# ADTPCB.net
KiCad netlist of a schematic drawn in Altium Designer
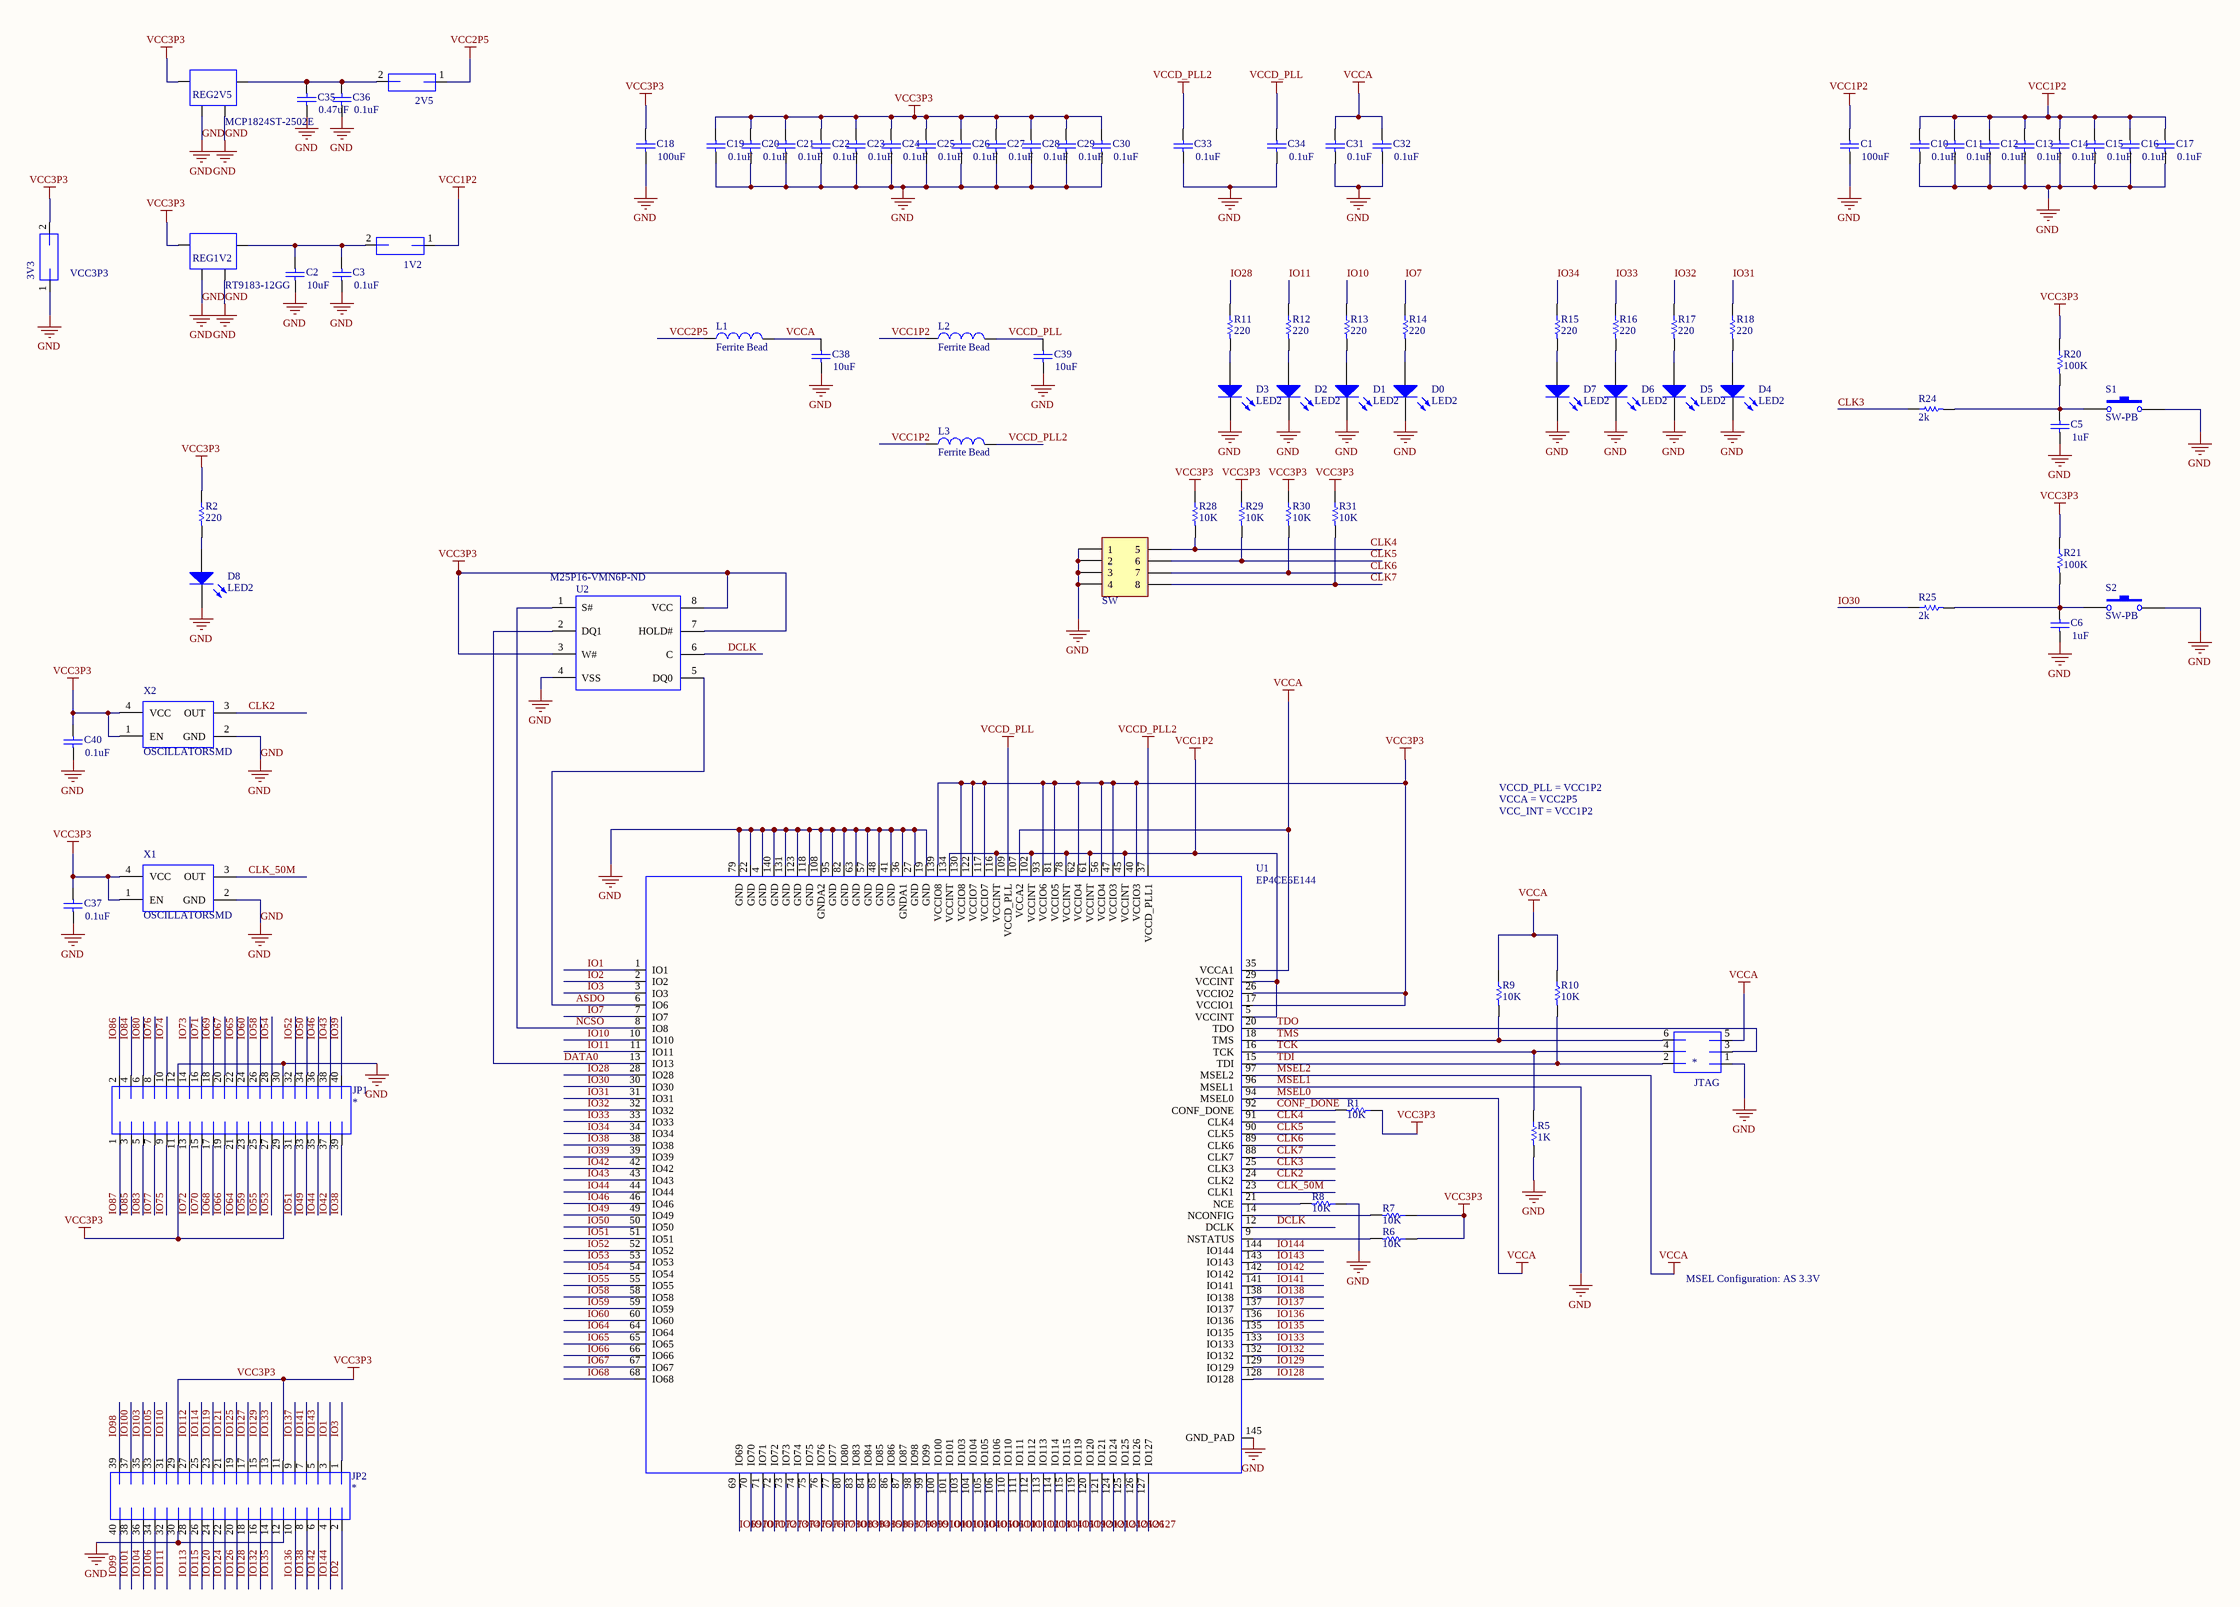
[diagram p0: ADTPCB.SchDoc]

(export (version "E")
  (design (tool "Eeschema 10.0.6"))
  (components
    (comp (ref "1V2")
      (value "1V2")
      (footprint "HDR1X2")
      (description "CONN HEADER 36POS .100 VERT TIN")
      (libsource (lib "jumper") (part "JP1Q"))
    )
    (comp (ref "2V5")
      (value "2V5")
      (footprint "HDR1X2")
      (description "CONN HEADER 36POS .100 VERT TIN")
      (libsource (lib "jumper") (part "JP1Q"))
    )
    (comp (ref "3V3")
      (value "VCC3P3")
      (footprint "HDR1X2")
      (description "CONN HEADER 36POS .100 VERT TIN")
      (libsource (lib "jumper") (part "JP1Q"))
    )
    (comp (ref "C1")
      (value "100uF")
      (footprint "C1206")
      (description "CAP CER 100UF 6.3V Y5V 1206")
      (fields (field (name "Comment") "Cap"))
      (libsource (lib "Miscellaneous Devices") (part "Cap"))
    )
    (comp (ref "C2")
      (value "10uF")
      (footprint "C0805")
      (description "CAP CER 10UF 10V Y5V 0805")
      (fields (field (name "Comment") "Cap"))
      (libsource (lib "Miscellaneous Devices") (part "Cap"))
    )
    (comp (ref "C3")
      (value "0.1uF")
      (footprint "C0805")
      (description "CAP CER 0.1UF 16V 10% X7R 0805")
      (fields (field (name "Comment") "Cap"))
      (libsource (lib "Miscellaneous Devices") (part "Cap"))
    )
    (comp (ref "C5")
      (value "1uF")
      (footprint "C0805")
      (description "CAP CER 1UF 16V Y5V 0805")
      (fields (field (name "Comment") "Cap"))
      (libsource (lib "Miscellaneous Devices") (part "Cap"))
    )
    (comp (ref "C6")
      (value "1uF")
      (footprint "C0805")
      (description "CAP CER 1UF 16V Y5V 0805")
      (fields (field (name "Comment") "Cap"))
      (libsource (lib "Miscellaneous Devices") (part "Cap"))
    )
    (comp (ref "C10")
      (value "0.1uF")
      (footprint "C0805")
      (description "CAP CER 0.1UF 16V 10% X7R 0805")
      (fields (field (name "Comment") "Cap"))
      (libsource (lib "Miscellaneous Devices") (part "Cap"))
    )
    (comp (ref "C11")
      (value "0.1uF")
      (footprint "C0805")
      (description "CAP CER 0.1UF 16V 10% X7R 0805")
      (fields (field (name "Comment") "Cap"))
      (libsource (lib "Miscellaneous Devices") (part "Cap"))
    )
    (comp (ref "C12")
      (value "0.1uF")
      (footprint "C0805")
      (description "CAP CER 0.1UF 16V 10% X7R 0805")
      (fields (field (name "Comment") "Cap"))
      (libsource (lib "Miscellaneous Devices") (part "Cap"))
    )
    (comp (ref "C13")
      (value "0.1uF")
      (footprint "C0805")
      (description "CAP CER 0.1UF 16V 10% X7R 0805")
      (fields (field (name "Comment") "Cap"))
      (libsource (lib "Miscellaneous Devices") (part "Cap"))
    )
    (comp (ref "C14")
      (value "0.1uF")
      (footprint "C0805")
      (description "CAP CER 0.1UF 16V 10% X7R 0805")
      (fields (field (name "Comment") "Cap"))
      (libsource (lib "Miscellaneous Devices") (part "Cap"))
    )
    (comp (ref "C15")
      (value "0.1uF")
      (footprint "C0805")
      (description "CAP CER 0.1UF 16V 10% X7R 0805")
      (fields (field (name "Comment") "Cap"))
      (libsource (lib "Miscellaneous Devices") (part "Cap"))
    )
    (comp (ref "C16")
      (value "0.1uF")
      (footprint "C0805")
      (description "CAP CER 0.1UF 16V 10% X7R 0805")
      (fields (field (name "Comment") "Cap"))
      (libsource (lib "Miscellaneous Devices") (part "Cap"))
    )
    (comp (ref "C17")
      (value "0.1uF")
      (footprint "C0805")
      (description "CAP CER 0.1UF 16V 10% X7R 0805")
      (fields (field (name "Comment") "Cap"))
      (libsource (lib "Miscellaneous Devices") (part "Cap"))
    )
    (comp (ref "C18")
      (value "100uF")
      (footprint "C1206")
      (description "CAP CER 100UF 6.3V Y5V 1206")
      (fields (field (name "Comment") "Cap"))
      (libsource (lib "Miscellaneous Devices") (part "Cap"))
    )
    (comp (ref "C19")
      (value "0.1uF")
      (footprint "C0805")
      (description "CAP CER 0.1UF 16V 10% X7R 0805")
      (fields (field (name "Comment") "Cap"))
      (libsource (lib "Miscellaneous Devices") (part "Cap"))
    )
    (comp (ref "C20")
      (value "0.1uF")
      (footprint "C0805")
      (description "CAP CER 0.1UF 16V 10% X7R 0805")
      (fields (field (name "Comment") "Cap"))
      (libsource (lib "Miscellaneous Devices") (part "Cap"))
    )
    (comp (ref "C21")
      (value "0.1uF")
      (footprint "C0805")
      (description "CAP CER 0.1UF 16V 10% X7R 0805")
      (fields (field (name "Comment") "Cap"))
      (libsource (lib "Miscellaneous Devices") (part "Cap"))
    )
    (comp (ref "C22")
      (value "0.1uF")
      (footprint "C0805")
      (description "CAP CER 0.1UF 16V 10% X7R 0805")
      (fields (field (name "Comment") "Cap"))
      (libsource (lib "Miscellaneous Devices") (part "Cap"))
    )
    (comp (ref "C23")
      (value "0.1uF")
      (footprint "C0805")
      (description "CAP CER 0.1UF 16V 10% X7R 0805")
      (fields (field (name "Comment") "Cap"))
      (libsource (lib "Miscellaneous Devices") (part "Cap"))
    )
    (comp (ref "C24")
      (value "0.1uF")
      (footprint "C0805")
      (description "CAP CER 0.1UF 16V 10% X7R 0805")
      (fields (field (name "Comment") "Cap"))
      (libsource (lib "Miscellaneous Devices") (part "Cap"))
    )
    (comp (ref "C25")
      (value "0.1uF")
      (footprint "C0805")
      (description "CAP CER 0.1UF 16V 10% X7R 0805")
      (fields (field (name "Comment") "Cap"))
      (libsource (lib "Miscellaneous Devices") (part "Cap"))
    )
    (comp (ref "C26")
      (value "0.1uF")
      (footprint "C0805")
      (description "CAP CER 0.1UF 16V 10% X7R 0805")
      (fields (field (name "Comment") "Cap"))
      (libsource (lib "Miscellaneous Devices") (part "Cap"))
    )
    (comp (ref "C27")
      (value "0.1uF")
      (footprint "C0805")
      (description "CAP CER 0.1UF 16V 10% X7R 0805")
      (fields (field (name "Comment") "Cap"))
      (libsource (lib "Miscellaneous Devices") (part "Cap"))
    )
    (comp (ref "C28")
      (value "0.1uF")
      (footprint "C0805")
      (description "CAP CER 0.1UF 16V 10% X7R 0805")
      (fields (field (name "Comment") "Cap"))
      (libsource (lib "Miscellaneous Devices") (part "Cap"))
    )
    (comp (ref "C29")
      (value "0.1uF")
      (footprint "C0805")
      (description "CAP CER 0.1UF 16V 10% X7R 0805")
      (fields (field (name "Comment") "Cap"))
      (libsource (lib "Miscellaneous Devices") (part "Cap"))
    )
    (comp (ref "C30")
      (value "0.1uF")
      (footprint "C0805")
      (description "CAP CER 0.1UF 16V 10% X7R 0805")
      (fields (field (name "Comment") "Cap"))
      (libsource (lib "Miscellaneous Devices") (part "Cap"))
    )
    (comp (ref "C31")
      (value "0.1uF")
      (footprint "C0805")
      (description "CAP CER 0.1UF 16V 10% X7R 0805")
      (fields (field (name "Comment") "Cap"))
      (libsource (lib "Miscellaneous Devices") (part "Cap"))
    )
    (comp (ref "C32")
      (value "0.1uF")
      (footprint "C0805")
      (description "CAP CER 0.1UF 16V 10% X7R 0805")
      (fields (field (name "Comment") "Cap"))
      (libsource (lib "Miscellaneous Devices") (part "Cap"))
    )
    (comp (ref "C33")
      (value "0.1uF")
      (footprint "C0805")
      (description "CAP CER 0.1UF 16V 10% X7R 0805")
      (fields (field (name "Comment") "Cap"))
      (libsource (lib "Miscellaneous Devices") (part "Cap"))
    )
    (comp (ref "C34")
      (value "0.1uF")
      (footprint "C0805")
      (description "CAP CER 0.1UF 16V 10% X7R 0805")
      (fields (field (name "Comment") "Cap"))
      (libsource (lib "Miscellaneous Devices") (part "Cap"))
    )
    (comp (ref "C35")
      (value "0.47uF")
      (footprint "C0805")
      (description "CAP CER 0.47UF 16V 10% X7R 0805")
      (fields (field (name "Comment") "Cap"))
      (libsource (lib "Miscellaneous Devices") (part "Cap"))
    )
    (comp (ref "C36")
      (value "0.1uF")
      (footprint "C0805")
      (description "CAP CER 0.1UF 16V 10% X7R 0805")
      (fields (field (name "Comment") "Cap"))
      (libsource (lib "Miscellaneous Devices") (part "Cap"))
    )
    (comp (ref "C37")
      (value "0.1uF")
      (footprint "C0805")
      (description "CAP CER 0.1UF 16V 10% X7R 0805")
      (fields (field (name "Comment") "Cap"))
      (libsource (lib "Miscellaneous Devices") (part "Cap"))
    )
    (comp (ref "C38")
      (value "10uF")
      (footprint "C0805")
      (description "CAP CER 10UF 10V Y5V 0805")
      (fields (field (name "Comment") "Cap"))
      (libsource (lib "Miscellaneous Devices") (part "Cap"))
    )
    (comp (ref "C39")
      (value "10uF")
      (footprint "C0805")
      (description "CAP CER 10UF 10V Y5V 0805")
      (fields (field (name "Comment") "Cap"))
      (libsource (lib "Miscellaneous Devices") (part "Cap"))
    )
    (comp (ref "C40")
      (value "0.1uF")
      (footprint "C0805")
      (description "CAP CER 0.1UF 16V 10% X7R 0805")
      (fields (field (name "Comment") "Cap"))
      (libsource (lib "Miscellaneous Devices") (part "Cap"))
    )
    (comp (ref "D0")
      (value "LED2")
      (footprint "CD2012-0805")
      (description "LED GREEN CLEAR THIN 0805 SMD")
      (libsource (lib "Miscellaneous Devices") (part "LED2"))
    )
    (comp (ref "D1")
      (value "LED2")
      (footprint "CD2012-0805")
      (description "LED GREEN CLEAR THIN 0805 SMD")
      (libsource (lib "Miscellaneous Devices") (part "LED2"))
    )
    (comp (ref "D2")
      (value "LED2")
      (footprint "CD2012-0805")
      (description "LED GREEN CLEAR THIN 0805 SMD")
      (libsource (lib "Miscellaneous Devices") (part "LED2"))
    )
    (comp (ref "D3")
      (value "LED2")
      (footprint "CD2012-0805")
      (description "LED GREEN CLEAR THIN 0805 SMD")
      (libsource (lib "Miscellaneous Devices") (part "LED2"))
    )
    (comp (ref "D4")
      (value "LED2")
      (footprint "CD2012-0805")
      (description "LED GREEN CLEAR THIN 0805 SMD")
      (libsource (lib "Miscellaneous Devices") (part "LED2"))
    )
    (comp (ref "D5")
      (value "LED2")
      (footprint "CD2012-0805")
      (description "LED GREEN CLEAR THIN 0805 SMD")
      (libsource (lib "Miscellaneous Devices") (part "LED2"))
    )
    (comp (ref "D6")
      (value "LED2")
      (footprint "CD2012-0805")
      (description "LED GREEN CLEAR THIN 0805 SMD")
      (libsource (lib "Miscellaneous Devices") (part "LED2"))
    )
    (comp (ref "D7")
      (value "LED2")
      (footprint "CD2012-0805")
      (description "LED GREEN CLEAR THIN 0805 SMD")
      (libsource (lib "Miscellaneous Devices") (part "LED2"))
    )
    (comp (ref "D8")
      (value "LED2")
      (footprint "CD2012-0805")
      (description "LED GREEN CLEAR THIN 0805 SMD")
      (libsource (lib "Miscellaneous Devices") (part "LED2"))
    )
    (comp (ref "JP1")
      (value "*")
      (footprint "HDR2X20")
      (description "CONN HEADER 36POS .100 VERT TIN")
      (libsource (lib "ADTBoard") (part "JP20Q"))
    )
    (comp (ref "JP2")
      (value "*")
      (footprint "HDR2X20")
      (description "CONN HEADER 36POS .100 VERT TIN")
      (libsource (lib "ADTBoard") (part "JP20Q"))
    )
    (comp (ref "JTAG")
      (value "*")
      (footprint "HDR1X6")
      (description "CONN HEADER 36POS .100 VERT TIN")
      (libsource (lib "jumper") (part "JP3Q"))
    )
    (comp (ref "L1")
      (value "Ferrite Bead")
      (footprint "2029")
      (description "FERRITE CHIP BEAD 600 OHM SMD")
      (libsource (lib "Miscellaneous Devices") (part "Inductor"))
    )
    (comp (ref "L2")
      (value "Ferrite Bead")
      (footprint "2029")
      (description "FERRITE CHIP BEAD 600 OHM SMD")
      (libsource (lib "Miscellaneous Devices") (part "Inductor"))
    )
    (comp (ref "L3")
      (value "Ferrite Bead")
      (footprint "2029")
      (description "FERRITE CHIP BEAD 600 OHM SMD")
      (libsource (lib "Miscellaneous Devices") (part "Inductor"))
    )
    (comp (ref "R1")
      (value "10K")
      (footprint "6-0805_L")
      (description "RES 10K OHM 1/8W 5% 0805 SMD")
      (fields (field (name "Comment") "Res Semi"))
      (libsource (lib "Miscellaneous Devices") (part "Res Semi"))
    )
    (comp (ref "R2")
      (value "220")
      (footprint "6-0805_L")
      (description "RES 220 OHM 1/8W 5% 0805 SMD")
      (fields (field (name "Comment") "Res Semi"))
      (libsource (lib "Miscellaneous Devices") (part "Res Semi"))
    )
    (comp (ref "R5")
      (value "1K")
      (footprint "6-0805_L")
      (description "RES 1.0K OHM 1/8W 5% 0805 SMD")
      (fields (field (name "Comment") "Res Semi"))
      (libsource (lib "Miscellaneous Devices") (part "Res Semi"))
    )
    (comp (ref "R6")
      (value "10K")
      (footprint "6-0805_L")
      (description "RES 10K OHM 1/8W 5% 0805 SMD")
      (fields (field (name "Comment") "Res Semi"))
      (libsource (lib "Miscellaneous Devices") (part "Res Semi"))
    )
    (comp (ref "R7")
      (value "10K")
      (footprint "6-0805_L")
      (description "RES 10K OHM 1/8W 5% 0805 SMD")
      (fields (field (name "Comment") "Res Semi"))
      (libsource (lib "Miscellaneous Devices") (part "Res Semi"))
    )
    (comp (ref "R8")
      (value "10K")
      (footprint "6-0805_L")
      (description "RES 10K OHM 1/8W 5% 0805 SMD")
      (fields (field (name "Comment") "Res Semi"))
      (libsource (lib "Miscellaneous Devices") (part "Res Semi"))
    )
    (comp (ref "R9")
      (value "10K")
      (footprint "6-0805_L")
      (description "RES 10K OHM 1/8W 5% 0805 SMD")
      (fields (field (name "Comment") "Res Semi"))
      (libsource (lib "Miscellaneous Devices") (part "Res Semi"))
    )
    (comp (ref "R10")
      (value "10K")
      (footprint "6-0805_L")
      (description "RES 10K OHM 1/8W 5% 0805 SMD")
      (fields (field (name "Comment") "Res Semi"))
      (libsource (lib "Miscellaneous Devices") (part "Res Semi"))
    )
    (comp (ref "R11")
      (value "220")
      (footprint "6-0805_L")
      (description "RES 220 OHM 1/8W 5% 0805 SMD")
      (fields (field (name "Comment") "Res Semi"))
      (libsource (lib "Miscellaneous Devices") (part "Res Semi"))
    )
    (comp (ref "R12")
      (value "220")
      (footprint "6-0805_L")
      (description "RES 220 OHM 1/8W 5% 0805 SMD")
      (fields (field (name "Comment") "Res Semi"))
      (libsource (lib "Miscellaneous Devices") (part "Res Semi"))
    )
    (comp (ref "R13")
      (value "220")
      (footprint "6-0805_L")
      (description "RES 220 OHM 1/8W 5% 0805 SMD")
      (fields (field (name "Comment") "Res Semi"))
      (libsource (lib "Miscellaneous Devices") (part "Res Semi"))
    )
    (comp (ref "R14")
      (value "220")
      (footprint "6-0805_L")
      (description "RES 220 OHM 1/8W 5% 0805 SMD")
      (fields (field (name "Comment") "Res Semi"))
      (libsource (lib "Miscellaneous Devices") (part "Res Semi"))
    )
    (comp (ref "R15")
      (value "220")
      (footprint "6-0805_L")
      (description "RES 220 OHM 1/8W 5% 0805 SMD")
      (fields (field (name "Comment") "Res Semi"))
      (libsource (lib "Miscellaneous Devices") (part "Res Semi"))
    )
    (comp (ref "R16")
      (value "220")
      (footprint "6-0805_L")
      (description "RES 220 OHM 1/8W 5% 0805 SMD")
      (fields (field (name "Comment") "Res Semi"))
      (libsource (lib "Miscellaneous Devices") (part "Res Semi"))
    )
    (comp (ref "R17")
      (value "220")
      (footprint "6-0805_L")
      (description "RES 220 OHM 1/8W 5% 0805 SMD")
      (fields (field (name "Comment") "Res Semi"))
      (libsource (lib "Miscellaneous Devices") (part "Res Semi"))
    )
    (comp (ref "R18")
      (value "220")
      (footprint "6-0805_L")
      (description "RES 220 OHM 1/8W 5% 0805 SMD")
      (fields (field (name "Comment") "Res Semi"))
      (libsource (lib "Miscellaneous Devices") (part "Res Semi"))
    )
    (comp (ref "R20")
      (value "100K")
      (footprint "6-0805_L")
      (description "RES 100K OHM 1/8W 5% 0805 SMD")
      (fields (field (name "Comment") "Res Semi"))
      (libsource (lib "Miscellaneous Devices") (part "Res Semi"))
    )
    (comp (ref "R21")
      (value "100K")
      (footprint "6-0805_L")
      (description "RES 100K OHM 1/8W 5% 0805 SMD")
      (fields (field (name "Comment") "Res Semi"))
      (libsource (lib "Miscellaneous Devices") (part "Res Semi"))
    )
    (comp (ref "R24")
      (value "2k")
      (footprint "6-0805_L")
      (description "RES 2K OHM 1/8W 5% 0805 SMD")
      (fields (field (name "Comment") "Res Semi"))
      (libsource (lib "Miscellaneous Devices") (part "Res Semi"))
    )
    (comp (ref "R25")
      (value "2k")
      (footprint "6-0805_L")
      (description "RES 2K OHM 1/8W 5% 0805 SMD")
      (fields (field (name "Comment") "Res Semi"))
      (libsource (lib "Miscellaneous Devices") (part "Res Semi"))
    )
    (comp (ref "R28")
      (value "10K")
      (footprint "6-0805_L")
      (description "RES 10K OHM 1/8W 5% 0805 SMD")
      (fields (field (name "Comment") "Res Semi"))
      (libsource (lib "Miscellaneous Devices") (part "Res Semi"))
    )
    (comp (ref "R29")
      (value "10K")
      (footprint "6-0805_L")
      (description "RES 10K OHM 1/8W 5% 0805 SMD")
      (fields (field (name "Comment") "Res Semi"))
      (libsource (lib "Miscellaneous Devices") (part "Res Semi"))
    )
    (comp (ref "R30")
      (value "10K")
      (footprint "6-0805_L")
      (description "RES 10K OHM 1/8W 5% 0805 SMD")
      (fields (field (name "Comment") "Res Semi"))
      (libsource (lib "Miscellaneous Devices") (part "Res Semi"))
    )
    (comp (ref "R31")
      (value "10K")
      (footprint "6-0805_L")
      (description "RES 10K OHM 1/8W 5% 0805 SMD")
      (fields (field (name "Comment") "Res Semi"))
      (libsource (lib "Miscellaneous Devices") (part "Res Semi"))
    )
    (comp (ref "REG1V2")
      (value "RT9183-12GG")
      (footprint "SOT223_M")
      (description "IC REG LDO 1.2V 1.5A SOT223")
      (libsource (lib "ADTBoard") (part "RT9183-12GG"))
    )
    (comp (ref "REG2V5")
      (value "MCP1824ST-2502E")
      (footprint "SOT223_M")
      (description "IC REG LDO 2.5V .3A SOT223-3")
      (libsource (lib "ADTBoard") (part "RT9183-12GG"))
    )
    (comp (ref "S1")
      (value "SW-PB")
      (footprint "EVQ-P7C01K")
      (description "SWITCH TACTILE SPST-NO 0.05A 12V")
      (libsource (lib "Miscellaneous Devices") (part "SW-PB"))
    )
    (comp (ref "S2")
      (value "SW-PB")
      (footprint "EVQ-P7C01K")
      (description "SWITCH TACTILE SPST-NO 0.05A 12V")
      (libsource (lib "Miscellaneous Devices") (part "SW-PB"))
    )
    (comp (ref "SW")
      (value "DIP")
      (footprint "DIP")
      (description "SWITCH DIP HALF PITCH 4POS")
      (libsource (lib "ADTPCB") (part "DIP"))
    )
    (comp (ref "U1")
      (value "EP4CE6E144")
      (footprint "EQFP144_M")
      (description "IC CYCLONE IV E FPGA 144EQFP")
      (libsource (lib "ADTPCB") (part "EP4CE6E144"))
    )
    (comp (ref "U2")
      (value "*")
      (footprint "SO8_M")
      (description "IC FLASH 16MBIT 75MHZ 8SOIC")
      (fields (field (name "SUPPLIER PART NUMBER 1") "M25P16-VMN6P-ND"))
      (libsource (lib "ADTBoard") (part "M25P16"))
    )
    (comp (ref "X1")
      (value "OSCILLATORSMD")
      (footprint "Oscillator SMD")
      (description "OSCILLATOR 50.00MHZ SMD")
      (libsource (lib "ADTPCB") (part "OSCILLATORSMD"))
    )
    (comp (ref "X2")
      (value "OSCILLATORSMD")
      (footprint "Oscillator SMD")
      (description "OSCILLATOR 50.00MHZ SMD")
      (libsource (lib "ADTPCB") (part "OSCILLATORSMD"))
    )
  )
  (nets
    (net (code "1") (name "/ASDO") (class "Default")
      (node (ref "U1") (pin "6") (pinfunction "IO6_6") (pintype "passive"))
      (node (ref "U2") (pin "5") (pinfunction "DQ0_5") (pintype "passive"))
    )
    (net (code "2") (name "/CLK2") (class "Default")
      (node (ref "U1") (pin "24") (pinfunction "CLK2_24") (pintype "passive"))
      (node (ref "X2") (pin "3") (pinfunction "OUT_3") (pintype "passive"))
    )
    (net (code "3") (name "/CLK3") (class "Default")
      (node (ref "R24") (pin "1") (pinfunction "1_1") (pintype "passive"))
      (node (ref "U1") (pin "25") (pinfunction "CLK3_25") (pintype "passive"))
    )
    (net (code "4") (name "/CLK4") (class "Default")
      (node (ref "R28") (pin "2") (pinfunction "2_2") (pintype "passive"))
      (node (ref "SW") (pin "5") (pinfunction "5_5") (pintype "passive"))
      (node (ref "U1") (pin "91") (pinfunction "CLK4_91") (pintype "passive"))
    )
    (net (code "5") (name "/CLK5") (class "Default")
      (node (ref "R29") (pin "2") (pinfunction "2_2") (pintype "passive"))
      (node (ref "SW") (pin "6") (pinfunction "6_6") (pintype "passive"))
      (node (ref "U1") (pin "90") (pinfunction "CLK5_90") (pintype "passive"))
    )
    (net (code "6") (name "/CLK6") (class "Default")
      (node (ref "R30") (pin "2") (pinfunction "2_2") (pintype "passive"))
      (node (ref "SW") (pin "7") (pinfunction "7_7") (pintype "passive"))
      (node (ref "U1") (pin "89") (pinfunction "CLK6_89") (pintype "passive"))
    )
    (net (code "7") (name "/CLK7") (class "Default")
      (node (ref "R31") (pin "2") (pinfunction "2_2") (pintype "passive"))
      (node (ref "SW") (pin "8") (pinfunction "8_8") (pintype "passive"))
      (node (ref "U1") (pin "88") (pinfunction "CLK7_88") (pintype "passive"))
    )
    (net (code "8") (name "/CLK_50M") (class "Default")
      (node (ref "U1") (pin "23") (pinfunction "CLK1_23") (pintype "passive"))
      (node (ref "X1") (pin "3") (pinfunction "OUT_3") (pintype "passive"))
    )
    (net (code "9") (name "/CONF_DONE") (class "Default")
      (node (ref "R1") (pin "2") (pinfunction "2_2") (pintype "passive"))
      (node (ref "U1") (pin "92") (pinfunction "CONF_DONE_92") (pintype "passive"))
    )
    (net (code "10") (name "/DATA0") (class "Default")
      (node (ref "U1") (pin "13") (pinfunction "IO13_13") (pintype "passive"))
      (node (ref "U2") (pin "2") (pinfunction "DQ1_2") (pintype "passive"))
    )
    (net (code "11") (name "/DCLK") (class "Default")
      (node (ref "U1") (pin "12") (pinfunction "DCLK_12") (pintype "passive"))
      (node (ref "U2") (pin "6") (pinfunction "C_6") (pintype "passive"))
    )
    (net (code "12") (name "/IO1") (class "Default")
      (node (ref "JP2") (pin "3") (pinfunction "3_3") (pintype "passive"))
      (node (ref "U1") (pin "1") (pinfunction "IO1_1") (pintype "passive"))
    )
    (net (code "13") (name "/IO2") (class "Default")
      (node (ref "JP2") (pin "2") (pinfunction "2_2") (pintype "passive"))
      (node (ref "U1") (pin "2") (pinfunction "IO2_2") (pintype "passive"))
    )
    (net (code "14") (name "/IO3") (class "Default")
      (node (ref "JP2") (pin "1") (pinfunction "1_1") (pintype "passive"))
      (node (ref "U1") (pin "3") (pinfunction "IO3_3") (pintype "passive"))
    )
    (net (code "15") (name "/IO7") (class "Default")
      (node (ref "R14") (pin "1") (pinfunction "1_1") (pintype "passive"))
      (node (ref "U1") (pin "7") (pinfunction "IO7_7") (pintype "passive"))
    )
    (net (code "16") (name "/IO10") (class "Default")
      (node (ref "R13") (pin "1") (pinfunction "1_1") (pintype "passive"))
      (node (ref "U1") (pin "10") (pinfunction "IO10_10") (pintype "passive"))
    )
    (net (code "17") (name "/IO11") (class "Default")
      (node (ref "R12") (pin "1") (pinfunction "1_1") (pintype "passive"))
      (node (ref "U1") (pin "11") (pinfunction "IO11_11") (pintype "passive"))
    )
    (net (code "18") (name "/IO28") (class "Default")
      (node (ref "R11") (pin "1") (pinfunction "1_1") (pintype "passive"))
      (node (ref "U1") (pin "28") (pinfunction "IO28_28") (pintype "passive"))
    )
    (net (code "19") (name "/IO30") (class "Default")
      (node (ref "R25") (pin "1") (pinfunction "1_1") (pintype "passive"))
      (node (ref "U1") (pin "30") (pinfunction "IO30_30") (pintype "passive"))
    )
    (net (code "20") (name "/IO31") (class "Default")
      (node (ref "R18") (pin "1") (pinfunction "1_1") (pintype "passive"))
      (node (ref "U1") (pin "31") (pinfunction "IO31_31") (pintype "passive"))
    )
    (net (code "21") (name "/IO32") (class "Default")
      (node (ref "R17") (pin "1") (pinfunction "1_1") (pintype "passive"))
      (node (ref "U1") (pin "32") (pinfunction "IO32_32") (pintype "passive"))
    )
    (net (code "22") (name "/IO33") (class "Default")
      (node (ref "R16") (pin "1") (pinfunction "1_1") (pintype "passive"))
      (node (ref "U1") (pin "33") (pinfunction "IO33_33") (pintype "passive"))
    )
    (net (code "23") (name "/IO34") (class "Default")
      (node (ref "R15") (pin "1") (pinfunction "1_1") (pintype "passive"))
      (node (ref "U1") (pin "34") (pinfunction "IO34_34") (pintype "passive"))
    )
    (net (code "24") (name "/IO38") (class "Default")
      (node (ref "JP1") (pin "39") (pinfunction "39_39") (pintype "passive"))
      (node (ref "U1") (pin "38") (pinfunction "IO38_38") (pintype "passive"))
    )
    (net (code "25") (name "/IO39") (class "Default")
      (node (ref "JP1") (pin "40") (pinfunction "40_40") (pintype "passive"))
      (node (ref "U1") (pin "39") (pinfunction "IO39_39") (pintype "passive"))
    )
    (net (code "26") (name "/IO42") (class "Default")
      (node (ref "JP1") (pin "37") (pinfunction "37_37") (pintype "passive"))
      (node (ref "U1") (pin "42") (pinfunction "IO42_42") (pintype "passive"))
    )
    (net (code "27") (name "/IO43") (class "Default")
      (node (ref "JP1") (pin "38") (pinfunction "38_38") (pintype "passive"))
      (node (ref "U1") (pin "43") (pinfunction "IO43_43") (pintype "passive"))
    )
    (net (code "28") (name "/IO44") (class "Default")
      (node (ref "JP1") (pin "35") (pinfunction "35_35") (pintype "passive"))
      (node (ref "U1") (pin "44") (pinfunction "IO44_44") (pintype "passive"))
    )
    (net (code "29") (name "/IO46") (class "Default")
      (node (ref "JP1") (pin "36") (pinfunction "36_36") (pintype "passive"))
      (node (ref "U1") (pin "46") (pinfunction "IO46_46") (pintype "passive"))
    )
    (net (code "30") (name "/IO49") (class "Default")
      (node (ref "JP1") (pin "33") (pinfunction "33_33") (pintype "passive"))
      (node (ref "U1") (pin "49") (pinfunction "IO49_49") (pintype "passive"))
    )
    (net (code "31") (name "/IO50") (class "Default")
      (node (ref "JP1") (pin "34") (pinfunction "34_34") (pintype "passive"))
      (node (ref "U1") (pin "50") (pinfunction "IO50_50") (pintype "passive"))
    )
    (net (code "32") (name "/IO51") (class "Default")
      (node (ref "JP1") (pin "31") (pinfunction "31_31") (pintype "passive"))
      (node (ref "U1") (pin "51") (pinfunction "IO51_51") (pintype "passive"))
    )
    (net (code "33") (name "/IO52") (class "Default")
      (node (ref "JP1") (pin "32") (pinfunction "32_32") (pintype "passive"))
      (node (ref "U1") (pin "52") (pinfunction "IO52_52") (pintype "passive"))
    )
    (net (code "34") (name "/IO53") (class "Default")
      (node (ref "JP1") (pin "27") (pinfunction "27_27") (pintype "passive"))
      (node (ref "U1") (pin "53") (pinfunction "IO53_53") (pintype "passive"))
    )
    (net (code "35") (name "/IO54") (class "Default")
      (node (ref "JP1") (pin "28") (pinfunction "28_28") (pintype "passive"))
      (node (ref "U1") (pin "54") (pinfunction "IO54_54") (pintype "passive"))
    )
    (net (code "36") (name "/IO55") (class "Default")
      (node (ref "JP1") (pin "25") (pinfunction "25_25") (pintype "passive"))
      (node (ref "U1") (pin "55") (pinfunction "IO55_55") (pintype "passive"))
    )
    (net (code "37") (name "/IO58") (class "Default")
      (node (ref "JP1") (pin "26") (pinfunction "26_26") (pintype "passive"))
      (node (ref "U1") (pin "58") (pinfunction "IO58_58") (pintype "passive"))
    )
    (net (code "38") (name "/IO59") (class "Default")
      (node (ref "JP1") (pin "23") (pinfunction "23_23") (pintype "passive"))
      (node (ref "U1") (pin "59") (pinfunction "IO59_59") (pintype "passive"))
    )
    (net (code "39") (name "/IO60") (class "Default")
      (node (ref "JP1") (pin "24") (pinfunction "24_24") (pintype "passive"))
      (node (ref "U1") (pin "60") (pinfunction "IO60_60") (pintype "passive"))
    )
    (net (code "40") (name "/IO64") (class "Default")
      (node (ref "JP1") (pin "21") (pinfunction "21_21") (pintype "passive"))
      (node (ref "U1") (pin "64") (pinfunction "IO64_64") (pintype "passive"))
    )
    (net (code "41") (name "/IO65") (class "Default")
      (node (ref "JP1") (pin "22") (pinfunction "22_22") (pintype "passive"))
      (node (ref "U1") (pin "65") (pinfunction "IO65_65") (pintype "passive"))
    )
    (net (code "42") (name "/IO66") (class "Default")
      (node (ref "JP1") (pin "19") (pinfunction "19_19") (pintype "passive"))
      (node (ref "U1") (pin "66") (pinfunction "IO66_66") (pintype "passive"))
    )
    (net (code "43") (name "/IO67") (class "Default")
      (node (ref "JP1") (pin "20") (pinfunction "20_20") (pintype "passive"))
      (node (ref "U1") (pin "67") (pinfunction "IO67_67") (pintype "passive"))
    )
    (net (code "44") (name "/IO68") (class "Default")
      (node (ref "JP1") (pin "17") (pinfunction "17_17") (pintype "passive"))
      (node (ref "U1") (pin "68") (pinfunction "IO68_68") (pintype "passive"))
    )
    (net (code "45") (name "/IO69") (class "Default")
      (node (ref "JP1") (pin "18") (pinfunction "18_18") (pintype "passive"))
      (node (ref "U1") (pin "69") (pinfunction "IO69_69") (pintype "passive"))
    )
    (net (code "46") (name "/IO70") (class "Default")
      (node (ref "JP1") (pin "15") (pinfunction "15_15") (pintype "passive"))
      (node (ref "U1") (pin "70") (pinfunction "IO70_70") (pintype "passive"))
    )
    (net (code "47") (name "/IO71") (class "Default")
      (node (ref "JP1") (pin "16") (pinfunction "16_16") (pintype "passive"))
      (node (ref "U1") (pin "71") (pinfunction "IO71_71") (pintype "passive"))
    )
    (net (code "48") (name "/IO72") (class "Default")
      (node (ref "JP1") (pin "13") (pinfunction "13_13") (pintype "passive"))
      (node (ref "U1") (pin "72") (pinfunction "IO72_72") (pintype "passive"))
    )
    (net (code "49") (name "/IO73") (class "Default")
      (node (ref "JP1") (pin "14") (pinfunction "14_14") (pintype "passive"))
      (node (ref "U1") (pin "73") (pinfunction "IO73_73") (pintype "passive"))
    )
    (net (code "50") (name "/IO74") (class "Default")
      (node (ref "JP1") (pin "10") (pinfunction "10_10") (pintype "passive"))
      (node (ref "U1") (pin "74") (pinfunction "IO74_74") (pintype "passive"))
    )
    (net (code "51") (name "/IO75") (class "Default")
      (node (ref "JP1") (pin "9") (pinfunction "9_9") (pintype "passive"))
      (node (ref "U1") (pin "75") (pinfunction "IO75_75") (pintype "passive"))
    )
    (net (code "52") (name "/IO76") (class "Default")
      (node (ref "JP1") (pin "8") (pinfunction "8_8") (pintype "passive"))
      (node (ref "U1") (pin "76") (pinfunction "IO76_76") (pintype "passive"))
    )
    (net (code "53") (name "/IO77") (class "Default")
      (node (ref "JP1") (pin "7") (pinfunction "7_7") (pintype "passive"))
      (node (ref "U1") (pin "77") (pinfunction "IO77_77") (pintype "passive"))
    )
    (net (code "54") (name "/IO80") (class "Default")
      (node (ref "JP1") (pin "6") (pinfunction "6_6") (pintype "passive"))
      (node (ref "U1") (pin "80") (pinfunction "IO80_80") (pintype "passive"))
    )
    (net (code "55") (name "/IO83") (class "Default")
      (node (ref "JP1") (pin "5") (pinfunction "5_5") (pintype "passive"))
      (node (ref "U1") (pin "83") (pinfunction "IO83_83") (pintype "passive"))
    )
    (net (code "56") (name "/IO84") (class "Default")
      (node (ref "JP1") (pin "4") (pinfunction "4_4") (pintype "passive"))
      (node (ref "U1") (pin "84") (pinfunction "IO84_84") (pintype "passive"))
    )
    (net (code "57") (name "/IO85") (class "Default")
      (node (ref "JP1") (pin "3") (pinfunction "3_3") (pintype "passive"))
      (node (ref "U1") (pin "85") (pinfunction "IO85_85") (pintype "passive"))
    )
    (net (code "58") (name "/IO86") (class "Default")
      (node (ref "JP1") (pin "2") (pinfunction "2_2") (pintype "passive"))
      (node (ref "U1") (pin "86") (pinfunction "IO86_86") (pintype "passive"))
    )
    (net (code "59") (name "/IO87") (class "Default")
      (node (ref "JP1") (pin "1") (pinfunction "1_1") (pintype "passive"))
      (node (ref "U1") (pin "87") (pinfunction "IO87_87") (pintype "passive"))
    )
    (net (code "60") (name "/IO98") (class "Default")
      (node (ref "JP2") (pin "39") (pinfunction "39_39") (pintype "passive"))
      (node (ref "U1") (pin "98") (pinfunction "IO98_98") (pintype "passive"))
    )
    (net (code "61") (name "/IO99") (class "Default")
      (node (ref "JP2") (pin "40") (pinfunction "40_40") (pintype "passive"))
      (node (ref "U1") (pin "99") (pinfunction "IO99_99") (pintype "passive"))
    )
    (net (code "62") (name "/IO100") (class "Default")
      (node (ref "JP2") (pin "37") (pinfunction "37_37") (pintype "passive"))
      (node (ref "U1") (pin "100") (pinfunction "IO100_100") (pintype "passive"))
    )
    (net (code "63") (name "/IO101") (class "Default")
      (node (ref "JP2") (pin "38") (pinfunction "38_38") (pintype "passive"))
      (node (ref "U1") (pin "101") (pinfunction "IO101_101") (pintype "passive"))
    )
    (net (code "64") (name "/IO103") (class "Default")
      (node (ref "JP2") (pin "35") (pinfunction "35_35") (pintype "passive"))
      (node (ref "U1") (pin "103") (pinfunction "IO103_103") (pintype "passive"))
    )
    (net (code "65") (name "/IO104") (class "Default")
      (node (ref "JP2") (pin "36") (pinfunction "36_36") (pintype "passive"))
      (node (ref "U1") (pin "104") (pinfunction "IO104_104") (pintype "passive"))
    )
    (net (code "66") (name "/IO105") (class "Default")
      (node (ref "JP2") (pin "33") (pinfunction "33_33") (pintype "passive"))
      (node (ref "U1") (pin "105") (pinfunction "IO105_105") (pintype "passive"))
    )
    (net (code "67") (name "/IO106") (class "Default")
      (node (ref "JP2") (pin "34") (pinfunction "34_34") (pintype "passive"))
      (node (ref "U1") (pin "106") (pinfunction "IO106_106") (pintype "passive"))
    )
    (net (code "68") (name "/IO110") (class "Default")
      (node (ref "JP2") (pin "31") (pinfunction "31_31") (pintype "passive"))
      (node (ref "U1") (pin "110") (pinfunction "IO110_110") (pintype "passive"))
    )
    (net (code "69") (name "/IO111") (class "Default")
      (node (ref "JP2") (pin "32") (pinfunction "32_32") (pintype "passive"))
      (node (ref "U1") (pin "111") (pinfunction "IO111_111") (pintype "passive"))
    )
    (net (code "70") (name "/IO112") (class "Default")
      (node (ref "JP2") (pin "27") (pinfunction "27_27") (pintype "passive"))
      (node (ref "U1") (pin "112") (pinfunction "IO112_112") (pintype "passive"))
    )
    (net (code "71") (name "/IO113") (class "Default")
      (node (ref "JP2") (pin "28") (pinfunction "28_28") (pintype "passive"))
      (node (ref "U1") (pin "113") (pinfunction "IO113_113") (pintype "passive"))
    )
    (net (code "72") (name "/IO114") (class "Default")
      (node (ref "JP2") (pin "25") (pinfunction "25_25") (pintype "passive"))
      (node (ref "U1") (pin "114") (pinfunction "IO114_114") (pintype "passive"))
    )
    (net (code "73") (name "/IO115") (class "Default")
      (node (ref "JP2") (pin "26") (pinfunction "26_26") (pintype "passive"))
      (node (ref "U1") (pin "115") (pinfunction "IO115_115") (pintype "passive"))
    )
    (net (code "74") (name "/IO119") (class "Default")
      (node (ref "JP2") (pin "23") (pinfunction "23_23") (pintype "passive"))
      (node (ref "U1") (pin "119") (pinfunction "IO119_119") (pintype "passive"))
    )
    (net (code "75") (name "/IO120") (class "Default")
      (node (ref "JP2") (pin "24") (pinfunction "24_24") (pintype "passive"))
      (node (ref "U1") (pin "120") (pinfunction "IO120_120") (pintype "passive"))
    )
    (net (code "76") (name "/IO121") (class "Default")
      (node (ref "JP2") (pin "21") (pinfunction "21_21") (pintype "passive"))
      (node (ref "U1") (pin "121") (pinfunction "IO121_121") (pintype "passive"))
    )
    (net (code "77") (name "/IO124") (class "Default")
      (node (ref "JP2") (pin "22") (pinfunction "22_22") (pintype "passive"))
      (node (ref "U1") (pin "124") (pinfunction "IO124_124") (pintype "passive"))
    )
    (net (code "78") (name "/IO125") (class "Default")
      (node (ref "JP2") (pin "19") (pinfunction "19_19") (pintype "passive"))
      (node (ref "U1") (pin "125") (pinfunction "IO125_125") (pintype "passive"))
    )
    (net (code "79") (name "/IO126") (class "Default")
      (node (ref "JP2") (pin "20") (pinfunction "20_20") (pintype "passive"))
      (node (ref "U1") (pin "126") (pinfunction "IO126_126") (pintype "passive"))
    )
    (net (code "80") (name "/IO127") (class "Default")
      (node (ref "JP2") (pin "17") (pinfunction "17_17") (pintype "passive"))
      (node (ref "U1") (pin "127") (pinfunction "IO127_127") (pintype "passive"))
    )
    (net (code "81") (name "/IO128") (class "Default")
      (node (ref "JP2") (pin "18") (pinfunction "18_18") (pintype "passive"))
      (node (ref "U1") (pin "128") (pinfunction "IO128_128") (pintype "passive"))
    )
    (net (code "82") (name "/IO129") (class "Default")
      (node (ref "JP2") (pin "15") (pinfunction "15_15") (pintype "passive"))
      (node (ref "U1") (pin "129") (pinfunction "IO129_129") (pintype "passive"))
    )
    (net (code "83") (name "/IO132") (class "Default")
      (node (ref "JP2") (pin "16") (pinfunction "16_16") (pintype "passive"))
      (node (ref "U1") (pin "132") (pinfunction "IO132_132") (pintype "passive"))
    )
    (net (code "84") (name "/IO133") (class "Default")
      (node (ref "JP2") (pin "13") (pinfunction "13_13") (pintype "passive"))
      (node (ref "U1") (pin "133") (pinfunction "IO133_133") (pintype "passive"))
    )
    (net (code "85") (name "/IO135") (class "Default")
      (node (ref "JP2") (pin "14") (pinfunction "14_14") (pintype "passive"))
      (node (ref "U1") (pin "135") (pinfunction "IO135_135") (pintype "passive"))
    )
    (net (code "86") (name "/IO136") (class "Default")
      (node (ref "JP2") (pin "10") (pinfunction "10_10") (pintype "passive"))
      (node (ref "U1") (pin "136") (pinfunction "IO136_136") (pintype "passive"))
    )
    (net (code "87") (name "/IO137") (class "Default")
      (node (ref "JP2") (pin "9") (pinfunction "9_9") (pintype "passive"))
      (node (ref "U1") (pin "137") (pinfunction "IO137_137") (pintype "passive"))
    )
    (net (code "88") (name "/IO138") (class "Default")
      (node (ref "JP2") (pin "8") (pinfunction "8_8") (pintype "passive"))
      (node (ref "U1") (pin "138") (pinfunction "IO138_138") (pintype "passive"))
    )
    (net (code "89") (name "/IO141") (class "Default")
      (node (ref "JP2") (pin "7") (pinfunction "7_7") (pintype "passive"))
      (node (ref "U1") (pin "141") (pinfunction "IO141_141") (pintype "passive"))
    )
    (net (code "90") (name "/IO142") (class "Default")
      (node (ref "JP2") (pin "6") (pinfunction "6_6") (pintype "passive"))
      (node (ref "U1") (pin "142") (pinfunction "IO142_142") (pintype "passive"))
    )
    (net (code "91") (name "/IO143") (class "Default")
      (node (ref "JP2") (pin "5") (pinfunction "5_5") (pintype "passive"))
      (node (ref "U1") (pin "143") (pinfunction "IO143_143") (pintype "passive"))
    )
    (net (code "92") (name "/IO144") (class "Default")
      (node (ref "JP2") (pin "4") (pinfunction "4_4") (pintype "passive"))
      (node (ref "U1") (pin "144") (pinfunction "IO144_144") (pintype "passive"))
    )
    (net (code "93") (name "/NCSO") (class "Default")
      (node (ref "U1") (pin "8") (pinfunction "IO8_8") (pintype "passive"))
      (node (ref "U2") (pin "1") (pinfunction "S#_1") (pintype "passive"))
    )
    (net (code "94") (name "/TCK") (class "Default")
      (node (ref "JTAG") (pin "4") (pinfunction "4_4") (pintype "passive"))
      (node (ref "R5") (pin "1") (pinfunction "1_1") (pintype "passive"))
      (node (ref "U1") (pin "16") (pinfunction "TCK_16") (pintype "passive"))
    )
    (net (code "95") (name "/TDI") (class "Default")
      (node (ref "JTAG") (pin "2") (pinfunction "2_2") (pintype "passive"))
      (node (ref "R10") (pin "2") (pinfunction "2_2") (pintype "passive"))
      (node (ref "U1") (pin "15") (pinfunction "TDI_15") (pintype "passive"))
    )
    (net (code "96") (name "/TDO") (class "Default")
      (node (ref "JTAG") (pin "3") (pinfunction "3_3") (pintype "passive"))
      (node (ref "U1") (pin "20") (pinfunction "TDO_20") (pintype "passive"))
    )
    (net (code "97") (name "/TMS") (class "Default")
      (node (ref "JTAG") (pin "6") (pinfunction "6_6") (pintype "passive"))
      (node (ref "R9") (pin "2") (pinfunction "2_2") (pintype "passive"))
      (node (ref "U1") (pin "18") (pinfunction "TMS_18") (pintype "passive"))
    )
    (net (code "98") (name "GND") (class "Default")
      (node (ref "3V3") (pin "1") (pinfunction "1_1") (pintype "passive"))
      (node (ref "C1") (pin "1") (pinfunction "1_1") (pintype "passive"))
      (node (ref "C10") (pin "1") (pinfunction "1_1") (pintype "passive"))
      (node (ref "C11") (pin "1") (pinfunction "1_1") (pintype "passive"))
      (node (ref "C12") (pin "1") (pinfunction "1_1") (pintype "passive"))
      (node (ref "C13") (pin "1") (pinfunction "1_1") (pintype "passive"))
      (node (ref "C14") (pin "1") (pinfunction "1_1") (pintype "passive"))
      (node (ref "C15") (pin "1") (pinfunction "1_1") (pintype "passive"))
      (node (ref "C16") (pin "1") (pinfunction "1_1") (pintype "passive"))
      (node (ref "C17") (pin "1") (pinfunction "1_1") (pintype "passive"))
      (node (ref "C18") (pin "1") (pinfunction "1_1") (pintype "passive"))
      (node (ref "C19") (pin "1") (pinfunction "1_1") (pintype "passive"))
      (node (ref "C2") (pin "1") (pinfunction "1_1") (pintype "passive"))
      (node (ref "C20") (pin "1") (pinfunction "1_1") (pintype "passive"))
      (node (ref "C21") (pin "1") (pinfunction "1_1") (pintype "passive"))
      (node (ref "C22") (pin "1") (pinfunction "1_1") (pintype "passive"))
      (node (ref "C23") (pin "1") (pinfunction "1_1") (pintype "passive"))
      (node (ref "C24") (pin "1") (pinfunction "1_1") (pintype "passive"))
      (node (ref "C25") (pin "1") (pinfunction "1_1") (pintype "passive"))
      (node (ref "C26") (pin "1") (pinfunction "1_1") (pintype "passive"))
      (node (ref "C27") (pin "1") (pinfunction "1_1") (pintype "passive"))
      (node (ref "C28") (pin "1") (pinfunction "1_1") (pintype "passive"))
      (node (ref "C29") (pin "1") (pinfunction "1_1") (pintype "passive"))
      (node (ref "C3") (pin "1") (pinfunction "1_1") (pintype "passive"))
      (node (ref "C30") (pin "1") (pinfunction "1_1") (pintype "passive"))
      (node (ref "C31") (pin "1") (pinfunction "1_1") (pintype "passive"))
      (node (ref "C32") (pin "1") (pinfunction "1_1") (pintype "passive"))
      (node (ref "C33") (pin "1") (pinfunction "1_1") (pintype "passive"))
      (node (ref "C34") (pin "1") (pinfunction "1_1") (pintype "passive"))
      (node (ref "C35") (pin "1") (pinfunction "1_1") (pintype "passive"))
      (node (ref "C36") (pin "1") (pinfunction "1_1") (pintype "passive"))
      (node (ref "C37") (pin "1") (pinfunction "1_1") (pintype "passive"))
      (node (ref "C38") (pin "1") (pinfunction "1_1") (pintype "passive"))
      (node (ref "C39") (pin "1") (pinfunction "1_1") (pintype "passive"))
      (node (ref "C40") (pin "1") (pinfunction "1_1") (pintype "passive"))
      (node (ref "C5") (pin "1") (pinfunction "1_1") (pintype "passive"))
      (node (ref "C6") (pin "1") (pinfunction "1_1") (pintype "passive"))
      (node (ref "D0") (pin "2") (pinfunction "K_2") (pintype "passive"))
      (node (ref "D1") (pin "2") (pinfunction "K_2") (pintype "passive"))
      (node (ref "D2") (pin "2") (pinfunction "K_2") (pintype "passive"))
      (node (ref "D3") (pin "2") (pinfunction "K_2") (pintype "passive"))
      (node (ref "D4") (pin "2") (pinfunction "K_2") (pintype "passive"))
      (node (ref "D5") (pin "2") (pinfunction "K_2") (pintype "passive"))
      (node (ref "D6") (pin "2") (pinfunction "K_2") (pintype "passive"))
      (node (ref "D7") (pin "2") (pinfunction "K_2") (pintype "passive"))
      (node (ref "D8") (pin "2") (pinfunction "K_2") (pintype "passive"))
      (node (ref "JP1") (pin "12") (pinfunction "12_12") (pintype "passive"))
      (node (ref "JP1") (pin "30") (pinfunction "30_30") (pintype "passive"))
      (node (ref "JP2") (pin "12") (pinfunction "12_12") (pintype "passive"))
      (node (ref "JP2") (pin "30") (pinfunction "30_30") (pintype "passive"))
      (node (ref "JTAG") (pin "1") (pinfunction "1_1") (pintype "passive"))
      (node (ref "R5") (pin "2") (pinfunction "2_2") (pintype "passive"))
      (node (ref "R8") (pin "1") (pinfunction "1_1") (pintype "passive"))
      (node (ref "REG1V2") (pin "2") (pinfunction "GND_2") (pintype "passive"))
      (node (ref "REG1V2") (pin "4") (pinfunction "GND1_4") (pintype "passive"))
      (node (ref "REG2V5") (pin "2") (pinfunction "GND_2") (pintype "passive"))
      (node (ref "REG2V5") (pin "4") (pinfunction "GND1_4") (pintype "passive"))
      (node (ref "S1") (pin "2") (pinfunction "2_2") (pintype "passive"))
      (node (ref "S2") (pin "2") (pinfunction "2_2") (pintype "passive"))
      (node (ref "SW") (pin "1") (pinfunction "1_1") (pintype "passive"))
      (node (ref "SW") (pin "2") (pinfunction "2_2") (pintype "passive"))
      (node (ref "SW") (pin "3") (pinfunction "3_3") (pintype "passive"))
      (node (ref "SW") (pin "4") (pinfunction "4_4") (pintype "passive"))
      (node (ref "U1") (pin "108") (pinfunction "GNDA2_108") (pintype "passive"))
      (node (ref "U1") (pin "118") (pinfunction "GND_118") (pintype "passive"))
      (node (ref "U1") (pin "123") (pinfunction "GND_123") (pintype "passive"))
      (node (ref "U1") (pin "131") (pinfunction "GND_131") (pintype "passive"))
      (node (ref "U1") (pin "140") (pinfunction "GND_140") (pintype "passive"))
      (node (ref "U1") (pin "145") (pinfunction "GND_PAD_145") (pintype "passive"))
      (node (ref "U1") (pin "19") (pinfunction "GND_19") (pintype "passive"))
      (node (ref "U1") (pin "22") (pinfunction "GND_22") (pintype "passive"))
      (node (ref "U1") (pin "27") (pinfunction "GND_27") (pintype "passive"))
      (node (ref "U1") (pin "36") (pinfunction "GNDA1_36") (pintype "passive"))
      (node (ref "U1") (pin "4") (pinfunction "GND_4") (pintype "passive"))
      (node (ref "U1") (pin "41") (pinfunction "GND_41") (pintype "passive"))
      (node (ref "U1") (pin "48") (pinfunction "GND_48") (pintype "passive"))
      (node (ref "U1") (pin "57") (pinfunction "GND_57") (pintype "passive"))
      (node (ref "U1") (pin "63") (pinfunction "GND_63") (pintype "passive"))
      (node (ref "U1") (pin "79") (pinfunction "GND_79") (pintype "passive"))
      (node (ref "U1") (pin "82") (pinfunction "GND_82") (pintype "passive"))
      (node (ref "U1") (pin "95") (pinfunction "GND_95") (pintype "passive"))
      (node (ref "U1") (pin "96") (pinfunction "MSEL1_96") (pintype "passive"))
      (node (ref "U2") (pin "4") (pinfunction "VSS_4") (pintype "passive"))
      (node (ref "X1") (pin "2") (pinfunction "GND_2") (pintype "passive"))
      (node (ref "X2") (pin "2") (pinfunction "GND_2") (pintype "passive"))
    )
    (net (code "99") (name "Net-(C5-Pad2)") (class "Default")
      (node (ref "C5") (pin "2") (pinfunction "2_2") (pintype "passive"))
      (node (ref "R20") (pin "2") (pinfunction "2_2") (pintype "passive"))
      (node (ref "R24") (pin "2") (pinfunction "2_2") (pintype "passive"))
      (node (ref "S1") (pin "1") (pinfunction "1_1") (pintype "passive"))
    )
    (net (code "100") (name "Net-(C6-Pad2)") (class "Default")
      (node (ref "C6") (pin "2") (pinfunction "2_2") (pintype "passive"))
      (node (ref "R21") (pin "2") (pinfunction "2_2") (pintype "passive"))
      (node (ref "R25") (pin "2") (pinfunction "2_2") (pintype "passive"))
      (node (ref "S2") (pin "1") (pinfunction "1_1") (pintype "passive"))
    )
    (net (code "101") (name "Net-(D0-A)") (class "Default")
      (node (ref "D0") (pin "1") (pinfunction "A_1") (pintype "passive"))
      (node (ref "R14") (pin "2") (pinfunction "2_2") (pintype "passive"))
    )
    (net (code "102") (name "Net-(D1-A)") (class "Default")
      (node (ref "D1") (pin "1") (pinfunction "A_1") (pintype "passive"))
      (node (ref "R13") (pin "2") (pinfunction "2_2") (pintype "passive"))
    )
    (net (code "103") (name "Net-(D2-A)") (class "Default")
      (node (ref "D2") (pin "1") (pinfunction "A_1") (pintype "passive"))
      (node (ref "R12") (pin "2") (pinfunction "2_2") (pintype "passive"))
    )
    (net (code "104") (name "Net-(D3-A)") (class "Default")
      (node (ref "D3") (pin "1") (pinfunction "A_1") (pintype "passive"))
      (node (ref "R11") (pin "2") (pinfunction "2_2") (pintype "passive"))
    )
    (net (code "105") (name "Net-(D4-A)") (class "Default")
      (node (ref "D4") (pin "1") (pinfunction "A_1") (pintype "passive"))
      (node (ref "R18") (pin "2") (pinfunction "2_2") (pintype "passive"))
    )
    (net (code "106") (name "Net-(D5-A)") (class "Default")
      (node (ref "D5") (pin "1") (pinfunction "A_1") (pintype "passive"))
      (node (ref "R17") (pin "2") (pinfunction "2_2") (pintype "passive"))
    )
    (net (code "107") (name "Net-(D6-A)") (class "Default")
      (node (ref "D6") (pin "1") (pinfunction "A_1") (pintype "passive"))
      (node (ref "R16") (pin "2") (pinfunction "2_2") (pintype "passive"))
    )
    (net (code "108") (name "Net-(D7-A)") (class "Default")
      (node (ref "D7") (pin "1") (pinfunction "A_1") (pintype "passive"))
      (node (ref "R15") (pin "2") (pinfunction "2_2") (pintype "passive"))
    )
    (net (code "109") (name "Net-(D8-A)") (class "Default")
      (node (ref "D8") (pin "1") (pinfunction "A_1") (pintype "passive"))
      (node (ref "R2") (pin "2") (pinfunction "2_2") (pintype "passive"))
    )
    (net (code "110") (name "Net-(REG1V2-OUT)") (class "Default")
      (node (ref "1V2") (pin "2") (pinfunction "2_2") (pintype "passive"))
      (node (ref "C2") (pin "2") (pinfunction "2_2") (pintype "passive"))
      (node (ref "C3") (pin "2") (pinfunction "2_2") (pintype "passive"))
      (node (ref "REG1V2") (pin "3") (pinfunction "OUT_3") (pintype "passive"))
    )
    (net (code "111") (name "Net-(REG2V5-OUT)") (class "Default")
      (node (ref "2V5") (pin "2") (pinfunction "2_2") (pintype "passive"))
      (node (ref "C35") (pin "2") (pinfunction "2_2") (pintype "passive"))
      (node (ref "C36") (pin "2") (pinfunction "2_2") (pintype "passive"))
      (node (ref "REG2V5") (pin "3") (pinfunction "OUT_3") (pintype "passive"))
    )
    (net (code "112") (name "Net-(U1-NCE)") (class "Default")
      (node (ref "R8") (pin "2") (pinfunction "2_2") (pintype "passive"))
      (node (ref "U1") (pin "21") (pinfunction "NCE_21") (pintype "passive"))
    )
    (net (code "113") (name "Net-(U1-NCONFIG)") (class "Default")
      (node (ref "R7") (pin "2") (pinfunction "2_2") (pintype "passive"))
      (node (ref "U1") (pin "14") (pinfunction "NCONFIG_14") (pintype "passive"))
    )
    (net (code "114") (name "Net-(U1-NSTATUS)") (class "Default")
      (node (ref "R6") (pin "2") (pinfunction "2_2") (pintype "passive"))
      (node (ref "U1") (pin "9") (pinfunction "NSTATUS_9") (pintype "passive"))
    )
    (net (code "115") (name "VCC1P2") (class "Default")
      (node (ref "1V2") (pin "1") (pinfunction "1_1") (pintype "passive"))
      (node (ref "C1") (pin "2") (pinfunction "2_2") (pintype "passive"))
      (node (ref "C10") (pin "2") (pinfunction "2_2") (pintype "passive"))
      (node (ref "C11") (pin "2") (pinfunction "2_2") (pintype "passive"))
      (node (ref "C12") (pin "2") (pinfunction "2_2") (pintype "passive"))
      (node (ref "C13") (pin "2") (pinfunction "2_2") (pintype "passive"))
      (node (ref "C14") (pin "2") (pinfunction "2_2") (pintype "passive"))
      (node (ref "C15") (pin "2") (pinfunction "2_2") (pintype "passive"))
      (node (ref "C16") (pin "2") (pinfunction "2_2") (pintype "passive"))
      (node (ref "C17") (pin "2") (pinfunction "2_2") (pintype "passive"))
      (node (ref "L2") (pin "1") (pinfunction "1_1") (pintype "passive"))
      (node (ref "L3") (pin "1") (pinfunction "1_1") (pintype "passive"))
      (node (ref "U1") (pin "102") (pinfunction "VCCINT_102") (pintype "passive"))
      (node (ref "U1") (pin "116") (pinfunction "VCCINT_116") (pintype "passive"))
      (node (ref "U1") (pin "134") (pinfunction "VCCINT_134") (pintype "passive"))
      (node (ref "U1") (pin "29") (pinfunction "VCCINT_29") (pintype "passive"))
      (node (ref "U1") (pin "45") (pinfunction "VCCINT_45") (pintype "passive"))
      (node (ref "U1") (pin "5") (pinfunction "VCCINT_5") (pintype "passive"))
      (node (ref "U1") (pin "61") (pinfunction "VCCINT_61") (pintype "passive"))
      (node (ref "U1") (pin "78") (pinfunction "VCCINT_78") (pintype "passive"))
    )
    (net (code "116") (name "VCC2P5") (class "Default")
      (node (ref "2V5") (pin "1") (pinfunction "1_1") (pintype "passive"))
      (node (ref "L1") (pin "1") (pinfunction "1_1") (pintype "passive"))
    )
    (net (code "117") (name "VCC3P3") (class "Default")
      (node (ref "3V3") (pin "2") (pinfunction "2_2") (pintype "passive"))
      (node (ref "C18") (pin "2") (pinfunction "2_2") (pintype "passive"))
      (node (ref "C19") (pin "2") (pinfunction "2_2") (pintype "passive"))
      (node (ref "C20") (pin "2") (pinfunction "2_2") (pintype "passive"))
      (node (ref "C21") (pin "2") (pinfunction "2_2") (pintype "passive"))
      (node (ref "C22") (pin "2") (pinfunction "2_2") (pintype "passive"))
      (node (ref "C23") (pin "2") (pinfunction "2_2") (pintype "passive"))
      (node (ref "C24") (pin "2") (pinfunction "2_2") (pintype "passive"))
      (node (ref "C25") (pin "2") (pinfunction "2_2") (pintype "passive"))
      (node (ref "C26") (pin "2") (pinfunction "2_2") (pintype "passive"))
      (node (ref "C27") (pin "2") (pinfunction "2_2") (pintype "passive"))
      (node (ref "C28") (pin "2") (pinfunction "2_2") (pintype "passive"))
      (node (ref "C29") (pin "2") (pinfunction "2_2") (pintype "passive"))
      (node (ref "C30") (pin "2") (pinfunction "2_2") (pintype "passive"))
      (node (ref "C37") (pin "2") (pinfunction "2_2") (pintype "passive"))
      (node (ref "C40") (pin "2") (pinfunction "2_2") (pintype "passive"))
      (node (ref "JP1") (pin "11") (pinfunction "11_11") (pintype "passive"))
      (node (ref "JP1") (pin "29") (pinfunction "29_29") (pintype "passive"))
      (node (ref "JP2") (pin "11") (pinfunction "11_11") (pintype "passive"))
      (node (ref "JP2") (pin "29") (pinfunction "29_29") (pintype "passive"))
      (node (ref "R1") (pin "1") (pinfunction "1_1") (pintype "passive"))
      (node (ref "R2") (pin "1") (pinfunction "1_1") (pintype "passive"))
      (node (ref "R20") (pin "1") (pinfunction "1_1") (pintype "passive"))
      (node (ref "R21") (pin "1") (pinfunction "1_1") (pintype "passive"))
      (node (ref "R28") (pin "1") (pinfunction "1_1") (pintype "passive"))
      (node (ref "R29") (pin "1") (pinfunction "1_1") (pintype "passive"))
      (node (ref "R30") (pin "1") (pinfunction "1_1") (pintype "passive"))
      (node (ref "R31") (pin "1") (pinfunction "1_1") (pintype "passive"))
      (node (ref "R6") (pin "1") (pinfunction "1_1") (pintype "passive"))
      (node (ref "R7") (pin "1") (pinfunction "1_1") (pintype "passive"))
      (node (ref "REG1V2") (pin "1") (pinfunction "IN_1") (pintype "passive"))
      (node (ref "REG2V5") (pin "1") (pinfunction "IN_1") (pintype "passive"))
      (node (ref "U1") (pin "117") (pinfunction "VCCIO7_117") (pintype "passive"))
      (node (ref "U1") (pin "122") (pinfunction "VCCIO7_122") (pintype "passive"))
      (node (ref "U1") (pin "130") (pinfunction "VCCIO8_130") (pintype "passive"))
      (node (ref "U1") (pin "139") (pinfunction "VCCIO8_139") (pintype "passive"))
      (node (ref "U1") (pin "17") (pinfunction "VCCIO1_17") (pintype "passive"))
      (node (ref "U1") (pin "26") (pinfunction "VCCIO2_26") (pintype "passive"))
      (node (ref "U1") (pin "40") (pinfunction "VCCIO3_40") (pintype "passive"))
      (node (ref "U1") (pin "47") (pinfunction "VCCIO3_47") (pintype "passive"))
      (node (ref "U1") (pin "56") (pinfunction "VCCIO4_56") (pintype "passive"))
      (node (ref "U1") (pin "62") (pinfunction "VCCIO4_62") (pintype "passive"))
      (node (ref "U1") (pin "81") (pinfunction "VCCIO5_81") (pintype "passive"))
      (node (ref "U1") (pin "93") (pinfunction "VCCIO6_93") (pintype "passive"))
      (node (ref "U2") (pin "3") (pinfunction "W#_3") (pintype "passive"))
      (node (ref "U2") (pin "7") (pinfunction "HOLD#_7") (pintype "passive"))
      (node (ref "U2") (pin "8") (pinfunction "VCC_8") (pintype "passive"))
      (node (ref "X1") (pin "1") (pinfunction "EN_1") (pintype "passive"))
      (node (ref "X1") (pin "4") (pinfunction "VCC_4") (pintype "passive"))
      (node (ref "X2") (pin "1") (pinfunction "EN_1") (pintype "passive"))
      (node (ref "X2") (pin "4") (pinfunction "VCC_4") (pintype "passive"))
    )
    (net (code "118") (name "VCCA") (class "Default")
      (node (ref "C31") (pin "2") (pinfunction "2_2") (pintype "passive"))
      (node (ref "C32") (pin "2") (pinfunction "2_2") (pintype "passive"))
      (node (ref "C38") (pin "2") (pinfunction "2_2") (pintype "passive"))
      (node (ref "JTAG") (pin "5") (pinfunction "5_5") (pintype "passive"))
      (node (ref "L1") (pin "2") (pinfunction "2_2") (pintype "passive"))
      (node (ref "R10") (pin "1") (pinfunction "1_1") (pintype "passive"))
      (node (ref "R9") (pin "1") (pinfunction "1_1") (pintype "passive"))
      (node (ref "U1") (pin "107") (pinfunction "VCCA2_107") (pintype "passive"))
      (node (ref "U1") (pin "35") (pinfunction "VCCA1_35") (pintype "passive"))
      (node (ref "U1") (pin "94") (pinfunction "MSEL0_94") (pintype "passive"))
      (node (ref "U1") (pin "97") (pinfunction "MSEL2_97") (pintype "passive"))
    )
    (net (code "119") (name "VCCD_PLL") (class "Default")
      (node (ref "C34") (pin "2") (pinfunction "2_2") (pintype "passive"))
      (node (ref "C39") (pin "2") (pinfunction "2_2") (pintype "passive"))
      (node (ref "L2") (pin "2") (pinfunction "2_2") (pintype "passive"))
      (node (ref "U1") (pin "109") (pinfunction "VCCD_PLL_109") (pintype "passive"))
    )
    (net (code "120") (name "VCCD_PLL2") (class "Default")
      (node (ref "C33") (pin "2") (pinfunction "2_2") (pintype "passive"))
      (node (ref "L3") (pin "2") (pinfunction "2_2") (pintype "passive"))
      (node (ref "U1") (pin "37") (pinfunction "VCCD_PLL1_37") (pintype "passive"))
    )
  )
)
